# Measure.net
KiCad netlist of a schematic drawn in Altium Designer
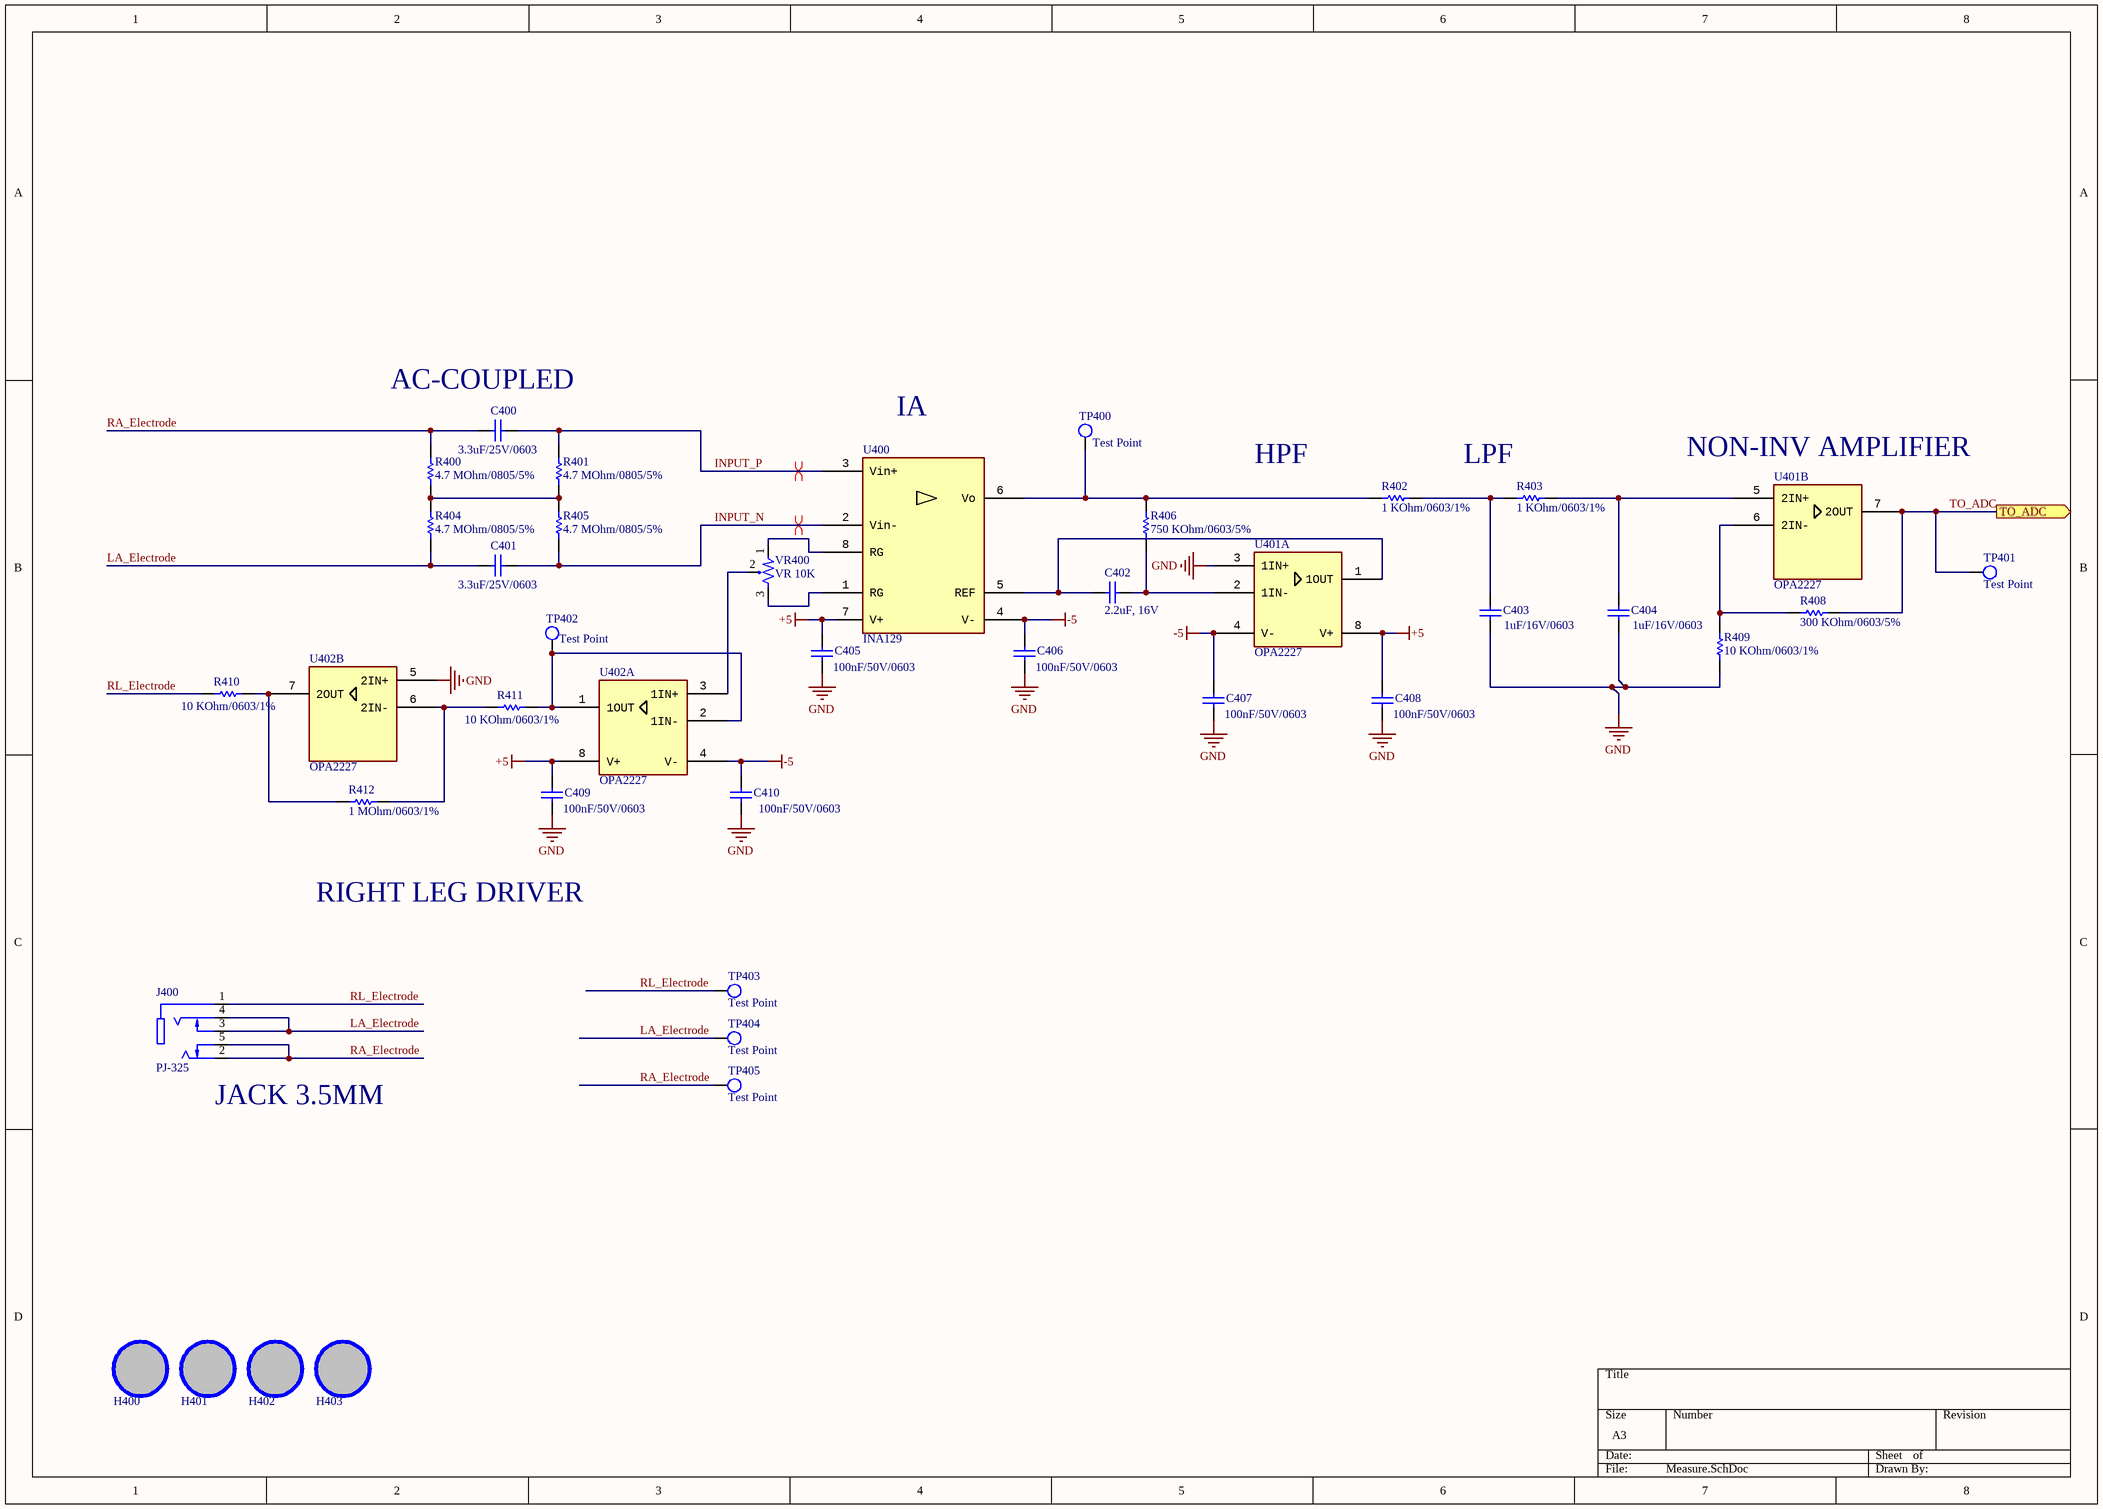
[diagram p0: Measure.SchDoc]

(export (version "E")
  (design (tool "Eeschema 10.0.6"))
  (components
    (comp (ref "C400")
      (value "3.3uF/25V/0603")
      (footprint "WCAP-CSGP_0805_H=1.25mm")
      (description "WCAP-CSGP Multilayer Ceramic Chip Capacitor, General Purpose, size 0805, X5R, 3.3uF, 25V")
      (fields
        (field (name "MANUFACTURER PART NUMBER") "885012107017")
        (field (name "MANUFACTURER") "Wurth Elektronik")
      )
      (libsource (lib "Altium_WCAP-CSGP (rev20a)") (part "885012107017"))
    )
    (comp (ref "C401")
      (value "3.3uF/25V/0603")
      (footprint "WCAP-CSGP_0805_H=1.25mm")
      (description "WCAP-CSGP Multilayer Ceramic Chip Capacitor, General Purpose, size 0805, X5R, 3.3uF, 25V")
      (fields
        (field (name "MANUFACTURER PART NUMBER") "885012107017")
        (field (name "MANUFACTURER") "Wurth Elektronik")
      )
      (libsource (lib "Altium_WCAP-CSGP (rev20a)") (part "885012107017"))
    )
    (comp (ref "C402")
      (value "2.2uF, 16V")
      (footprint "WCAP-CSGP_0603_H=0.8mm_Reflow")
      (description "WCAP-CSGP Multilayer Ceramic Chip Capacitor, General Purpose, size 0603, X5R, 2.2uF, 16V")
      (fields
        (field (name "MANUFACTURER PART NUMBER") "885012106018")
        (field (name "MANUFACTURER") "Wurth Elektronik")
      )
      (libsource (lib "Altium_WCAP-CSGP (rev20a)") (part "885012106018"))
    )
    (comp (ref "C403")
      (value "1uF/16V/0603")
      (footprint "WCAP-CSGP_0603_H=0.8mm_Reflow")
      (description "WCAP-CSGP Multilayer Ceramic Chip Capacitor, General Purpose, size 0603, X5R, 1uF, 16V")
      (fields
        (field (name "MANUFACTURER PART NUMBER") "885012106017")
        (field (name "MANUFACTURER") "Wurth Elektronik")
      )
      (libsource (lib "Altium_WCAP-CSGP (rev20a)") (part "885012106017"))
    )
    (comp (ref "C404")
      (value "1uF/16V/0603")
      (footprint "WCAP-CSGP_0603_H=0.8mm_Reflow")
      (description "WCAP-CSGP Multilayer Ceramic Chip Capacitor, General Purpose, size 0603, X5R, 1uF, 16V")
      (fields
        (field (name "MANUFACTURER PART NUMBER") "885012106017")
        (field (name "MANUFACTURER") "Wurth Elektronik")
      )
      (libsource (lib "Altium_WCAP-CSGP (rev20a)") (part "885012106017"))
    )
    (comp (ref "C405")
      (value "100nF/50V/0603")
      (footprint "WCAP-CSGP_0603_H=0.8mm_Reflow")
      (description "WCAP-CSGP Multilayer Ceramic Chip Capacitor, General Purpose, size 0603, X7R, 100nF, 25V")
      (fields
        (field (name "MANUFACTURER PART NUMBER") "885012206071")
        (field (name "MANUFACTURER") "Wurth Elektronik")
      )
      (libsource (lib "Altium_WCAP-CSGP (rev20a)") (part "885012206071"))
    )
    (comp (ref "C406")
      (value "100nF/50V/0603")
      (footprint "WCAP-CSGP_0603_H=0.8mm_Reflow")
      (description "WCAP-CSGP Multilayer Ceramic Chip Capacitor, General Purpose, size 0603, X7R, 100nF, 25V")
      (fields
        (field (name "MANUFACTURER PART NUMBER") "885012206071")
        (field (name "MANUFACTURER") "Wurth Elektronik")
      )
      (libsource (lib "Altium_WCAP-CSGP (rev20a)") (part "885012206071"))
    )
    (comp (ref "C407")
      (value "100nF/50V/0603")
      (footprint "WCAP-CSGP_0603_H=0.8mm_Reflow")
      (description "WCAP-CSGP Multilayer Ceramic Chip Capacitor, General Purpose, size 0603, X7R, 100nF, 25V")
      (fields
        (field (name "MANUFACTURER PART NUMBER") "885012206071")
        (field (name "MANUFACTURER") "Wurth Elektronik")
      )
      (libsource (lib "Altium_WCAP-CSGP (rev20a)") (part "885012206071"))
    )
    (comp (ref "C408")
      (value "100nF/50V/0603")
      (footprint "WCAP-CSGP_0603_H=0.8mm_Reflow")
      (description "WCAP-CSGP Multilayer Ceramic Chip Capacitor, General Purpose, size 0603, X7R, 100nF, 25V")
      (fields
        (field (name "MANUFACTURER PART NUMBER") "885012206071")
        (field (name "MANUFACTURER") "Wurth Elektronik")
      )
      (libsource (lib "Altium_WCAP-CSGP (rev20a)") (part "885012206071"))
    )
    (comp (ref "C409")
      (value "100nF/50V/0603")
      (footprint "WCAP-CSGP_0603_H=0.8mm_Reflow")
      (description "WCAP-CSGP Multilayer Ceramic Chip Capacitor, General Purpose, size 0603, X7R, 100nF, 25V")
      (fields
        (field (name "MANUFACTURER PART NUMBER") "885012206071")
        (field (name "MANUFACTURER") "Wurth Elektronik")
      )
      (libsource (lib "Altium_WCAP-CSGP (rev20a)") (part "885012206071"))
    )
    (comp (ref "C410")
      (value "100nF/50V/0603")
      (footprint "WCAP-CSGP_0603_H=0.8mm_Reflow")
      (description "WCAP-CSGP Multilayer Ceramic Chip Capacitor, General Purpose, size 0603, X7R, 100nF, 25V")
      (fields
        (field (name "MANUFACTURER PART NUMBER") "885012206071")
        (field (name "MANUFACTURER") "Wurth Elektronik")
      )
      (libsource (lib "Altium_WCAP-CSGP (rev20a)") (part "885012206071"))
    )
    (comp (ref "H400")
      (value "Hole")
      (footprint "LO KHOAN 3MM")
      (description "Hole 3mm")
      (libsource (lib "PIF_Library") (part "Hole"))
    )
    (comp (ref "H401")
      (value "Hole")
      (footprint "LO KHOAN 3MM")
      (description "Hole 3mm")
      (libsource (lib "PIF_Library") (part "Hole"))
    )
    (comp (ref "H402")
      (value "Hole")
      (footprint "LO KHOAN 3MM")
      (description "Hole 3mm")
      (libsource (lib "PIF_Library") (part "Hole"))
    )
    (comp (ref "H403")
      (value "Hole")
      (footprint "LO KHOAN 3MM")
      (description "Hole 3mm")
      (libsource (lib "PIF_Library") (part "Hole"))
    )
    (comp (ref "J400")
      (value "PJ-325")
      (footprint "3.5 mm, Strereo")
      (description "Jack 3.5 3-Pole 5-Pin")
      (fields (field (name "Comment") "PJ-324"))
      (libsource (lib "Giang's Libs") (part "PJ-324"))
    )
    (comp (ref "R400")
      (value "4.7 MOhm/0805/5%")
      (footprint "R0805")
      (description "Code 475, 1/8W")
      (fields (field (name "Comment") "Resistor 4.7 MOhm 0805 5%"))
      (libsource (lib "Giang_Resistor") (part "Resistor 4.7 MOhm 0805 5%"))
    )
    (comp (ref "R401")
      (value "4.7 MOhm/0805/5%")
      (footprint "R0805")
      (description "Code 475, 1/8W")
      (fields (field (name "Comment") "Resistor 4.7 MOhm 0805 5%"))
      (libsource (lib "Giang_Resistor") (part "Resistor 4.7 MOhm 0805 5%"))
    )
    (comp (ref "R402")
      (value "1 KOhm/0603/1%")
      (footprint "R0603")
      (description "Code 102, 1/10W")
      (fields (field (name "Comment") "Resistor 1 KOhm 0603 1%"))
      (libsource (lib "Giang_Resistor") (part "Resistor 1 KOhm 0603 1%"))
    )
    (comp (ref "R403")
      (value "1 KOhm/0603/1%")
      (footprint "R0603")
      (description "Code 102, 1/10W")
      (fields (field (name "Comment") "Resistor 1 KOhm 0603 1%"))
      (libsource (lib "Giang_Resistor") (part "Resistor 1 KOhm 0603 1%"))
    )
    (comp (ref "R404")
      (value "4.7 MOhm/0805/5%")
      (footprint "R0805")
      (description "Code 475, 1/8W")
      (fields (field (name "Comment") "Resistor 4.7 MOhm 0805 5%"))
      (libsource (lib "Giang_Resistor") (part "Resistor 4.7 MOhm 0805 5%"))
    )
    (comp (ref "R405")
      (value "4.7 MOhm/0805/5%")
      (footprint "R0805")
      (description "Code 475, 1/8W")
      (fields (field (name "Comment") "Resistor 4.7 MOhm 0805 5%"))
      (libsource (lib "Giang_Resistor") (part "Resistor 4.7 MOhm 0805 5%"))
    )
    (comp (ref "R406")
      (value "750 KOhm/0603/5%")
      (footprint "R0603")
      (description "Code 754, 1/10W")
      (fields (field (name "Comment") "Resistor 750 KOhm 0603 5%"))
      (libsource (lib "Giang_Resistor") (part "Resistor 750 KOhm 0603 5%"))
    )
    (comp (ref "R408")
      (value "300 KOhm/0603/5%")
      (footprint "R0603")
      (description "Code 304, 1/10W")
      (fields (field (name "Comment") "Resistor 300 KOhm 0603 5%"))
      (libsource (lib "Giang_Resistor") (part "Resistor 300 KOhm 0603 5%"))
    )
    (comp (ref "R409")
      (value "10 KOhm/0603/1%")
      (footprint "R0603")
      (description "Code 103, 1/10W")
      (fields (field (name "Comment") "Resistor 10 KOhm 0603 1%"))
      (libsource (lib "Giang_Resistor") (part "Resistor 10 KOhm 0603 1%"))
    )
    (comp (ref "R410")
      (value "10 KOhm/0603/1%")
      (footprint "R0603")
      (description "Code 103, 1/10W")
      (fields (field (name "Comment") "Resistor 10 KOhm 0603 1%"))
      (libsource (lib "Giang_Resistor") (part "Resistor 10 KOhm 0603 1%"))
    )
    (comp (ref "R411")
      (value "10 KOhm/0603/1%")
      (footprint "R0603")
      (description "Code 103, 1/10W")
      (fields (field (name "Comment") "Resistor 10 KOhm 0603 1%"))
      (libsource (lib "Giang_Resistor") (part "Resistor 10 KOhm 0603 1%"))
    )
    (comp (ref "R412")
      (value "1 MOhm/0603/1%")
      (footprint "R0603")
      (description "Code 105, 1/10W")
      (fields (field (name "Comment") "Resistor 1 MOhm 0603 1%"))
      (libsource (lib "Giang_Resistor") (part "Resistor 1 MOhm 0603 1%"))
    )
    (comp (ref "TP400")
      (value "Test Point")
      (footprint "TP")
      (libsource (lib "PIF_Library") (part "Test Point"))
    )
    (comp (ref "TP401")
      (value "Test Point")
      (footprint "TP")
      (libsource (lib "PIF_Library") (part "Test Point"))
    )
    (comp (ref "TP402")
      (value "Test Point")
      (footprint "TP")
      (libsource (lib "PIF_Library") (part "Test Point"))
    )
    (comp (ref "TP403")
      (value "Test Point")
      (footprint "TP")
      (libsource (lib "PIF_Library") (part "Test Point"))
    )
    (comp (ref "TP404")
      (value "Test Point")
      (footprint "TP")
      (libsource (lib "PIF_Library") (part "Test Point"))
    )
    (comp (ref "TP405")
      (value "Test Point")
      (footprint "TP")
      (libsource (lib "PIF_Library") (part "Test Point"))
    )
    (comp (ref "U400")
      (value "INA129")
      (footprint "SOIC-8")
      (description "Precision, Low Power Instrumentation Amplifiers")
      (libsource (lib "Giang_OPAMP") (part "INA129"))
    )
    (comp (ref "U401")
      (value "OPA2227")
      (footprint "SOIC-8")
      (description "High-Precision, Low-Noise Operational Amplifiers")
      (libsource (lib "Giang_OPAMP") (part "OPA2227"))
    )
    (comp (ref "U402")
      (value "OPA2227")
      (footprint "SOIC-8")
      (description "High-Precision, Low-Noise Operational Amplifiers")
      (libsource (lib "") (part "OPA2227_1"))
    )
    (comp (ref "VR400")
      (value "VR 10K")
      (footprint "VARISTOR 2")
      (description "Var Resistor")
      (fields (field (name "Comment") "10K"))
      (libsource (lib "PIF_Library") (part "Var Resistor"))
    )
  )
  (nets
    (net (code "1") (name "+5") (class "Default")
      (node (ref "C405") (pin "2") (pinfunction "2_2") (pintype "passive"))
      (node (ref "C408") (pin "1") (pinfunction "1_1") (pintype "passive"))
      (node (ref "C409") (pin "2") (pinfunction "2_2") (pintype "passive"))
      (node (ref "U400") (pin "7") (pinfunction "V+_7") (pintype "passive"))
      (node (ref "U401") (pin "8") (pinfunction "V+_8") (pintype "passive"))
      (node (ref "U402") (pin "8") (pinfunction "V+_8") (pintype "passive"))
    )
    (net (code "2") (name "-5") (class "Default")
      (node (ref "C406") (pin "1") (pinfunction "1_1") (pintype "passive"))
      (node (ref "C407") (pin "2") (pinfunction "2_2") (pintype "passive"))
      (node (ref "C410") (pin "1") (pinfunction "1_1") (pintype "passive"))
      (node (ref "U400") (pin "4") (pinfunction "V-_4") (pintype "passive"))
      (node (ref "U401") (pin "4") (pinfunction "V-_4") (pintype "passive"))
      (node (ref "U402") (pin "4") (pinfunction "V-_4") (pintype "passive"))
    )
    (net (code "3") (name "/INPUT_N") (class "Default")
      (node (ref "C401") (pin "2") (pinfunction "2_2") (pintype "passive"))
      (node (ref "R405") (pin "1") (pinfunction "1_1") (pintype "passive"))
      (node (ref "U400") (pin "2") (pinfunction "Vin-_2") (pintype "passive"))
    )
    (net (code "4") (name "/INPUT_P") (class "Default")
      (node (ref "C400") (pin "2") (pinfunction "2_2") (pintype "passive"))
      (node (ref "R401") (pin "2") (pinfunction "2_2") (pintype "passive"))
      (node (ref "U400") (pin "3") (pinfunction "Vin+_3") (pintype "passive"))
    )
    (net (code "5") (name "/LA_Electrode") (class "Default")
      (node (ref "C401") (pin "1") (pinfunction "1_1") (pintype "passive"))
      (node (ref "J400") (pin "3") (pinfunction "3_3") (pintype "passive"))
      (node (ref "J400") (pin "4") (pinfunction "4_4") (pintype "passive"))
      (node (ref "R404") (pin "1") (pinfunction "1_1") (pintype "passive"))
      (node (ref "TP404") (pin "TP1") (pinfunction "0_TP1") (pintype "passive"))
    )
    (net (code "6") (name "/RA_Electrode") (class "Default")
      (node (ref "C400") (pin "1") (pinfunction "1_1") (pintype "passive"))
      (node (ref "J400") (pin "2") (pinfunction "2_2") (pintype "passive"))
      (node (ref "J400") (pin "5") (pinfunction "5_5") (pintype "passive"))
      (node (ref "R400") (pin "2") (pinfunction "2_2") (pintype "passive"))
      (node (ref "TP405") (pin "TP1") (pinfunction "0_TP1") (pintype "passive"))
    )
    (net (code "7") (name "/RL_Electrode") (class "Default")
      (node (ref "J400") (pin "1") (pinfunction "1_1") (pintype "passive"))
      (node (ref "R410") (pin "1") (pinfunction "1_1") (pintype "passive"))
      (node (ref "TP403") (pin "TP1") (pinfunction "0_TP1") (pintype "passive"))
    )
    (net (code "8") (name "/TO_ADC") (class "Default")
      (node (ref "R408") (pin "2") (pinfunction "2_2") (pintype "passive"))
      (node (ref "TP401") (pin "TP1") (pinfunction "0_TP1") (pintype "passive"))
      (node (ref "U401") (pin "7") (pinfunction "2OUT_7") (pintype "passive"))
    )
    (net (code "9") (name "GND") (class "Default")
      (node (ref "C403") (pin "1") (pinfunction "1_1") (pintype "passive"))
      (node (ref "C404") (pin "1") (pinfunction "1_1") (pintype "passive"))
      (node (ref "C405") (pin "1") (pinfunction "1_1") (pintype "passive"))
      (node (ref "C406") (pin "2") (pinfunction "2_2") (pintype "passive"))
      (node (ref "C407") (pin "1") (pinfunction "1_1") (pintype "passive"))
      (node (ref "C408") (pin "2") (pinfunction "2_2") (pintype "passive"))
      (node (ref "C409") (pin "1") (pinfunction "1_1") (pintype "passive"))
      (node (ref "C410") (pin "2") (pinfunction "2_2") (pintype "passive"))
      (node (ref "R409") (pin "1") (pinfunction "1_1") (pintype "passive"))
      (node (ref "U401") (pin "3") (pinfunction "1IN+_3") (pintype "passive"))
      (node (ref "U402") (pin "5") (pinfunction "2IN+_5") (pintype "passive"))
    )
    (net (code "10") (name "Net-(C403-Pad2)") (class "Default")
      (node (ref "C403") (pin "2") (pinfunction "2_2") (pintype "passive"))
      (node (ref "R402") (pin "2") (pinfunction "2_2") (pintype "passive"))
      (node (ref "R403") (pin "1") (pinfunction "1_1") (pintype "passive"))
    )
    (net (code "11") (name "Net-(R400-Pad1)") (class "Default")
      (node (ref "R400") (pin "1") (pinfunction "1_1") (pintype "passive"))
      (node (ref "R401") (pin "1") (pinfunction "1_1") (pintype "passive"))
      (node (ref "R404") (pin "2") (pinfunction "2_2") (pintype "passive"))
      (node (ref "R405") (pin "2") (pinfunction "2_2") (pintype "passive"))
    )
    (net (code "12") (name "Net-(TP400-0)") (class "Default")
      (node (ref "R402") (pin "1") (pinfunction "1_1") (pintype "passive"))
      (node (ref "R406") (pin "2") (pinfunction "2_2") (pintype "passive"))
      (node (ref "TP400") (pin "TP1") (pinfunction "0_TP1") (pintype "passive"))
      (node (ref "U400") (pin "6") (pinfunction "Vo_6") (pintype "passive"))
    )
    (net (code "13") (name "Net-(TP402-0)") (class "Default")
      (node (ref "R411") (pin "2") (pinfunction "2_2") (pintype "passive"))
      (node (ref "TP402") (pin "TP1") (pinfunction "0_TP1") (pintype "passive"))
      (node (ref "U402") (pin "1") (pinfunction "1OUT_1") (pintype "passive"))
      (node (ref "U402") (pin "2") (pinfunction "1IN-_2") (pintype "passive"))
    )
    (net (code "14") (name "Net-(U400-REF)") (class "Default")
      (node (ref "C402") (pin "2") (pinfunction "2_2") (pintype "passive"))
      (node (ref "U400") (pin "5") (pinfunction "REF_5") (pintype "passive"))
      (node (ref "U401") (pin "1") (pinfunction "1OUT_1") (pintype "passive"))
    )
    (net (code "15") (name "Net-(U400-RG-Pad1)") (class "Default")
      (node (ref "U400") (pin "1") (pinfunction "RG_1") (pintype "passive"))
      (node (ref "VR400") (pin "3") (pinfunction "3_3") (pintype "passive"))
    )
    (net (code "16") (name "Net-(U400-RG-Pad8)") (class "Default")
      (node (ref "U400") (pin "8") (pinfunction "RG_8") (pintype "passive"))
      (node (ref "VR400") (pin "1") (pinfunction "1_1") (pintype "passive"))
    )
    (net (code "17") (name "Net-(U401A-1IN-)") (class "Default")
      (node (ref "C402") (pin "1") (pinfunction "1_1") (pintype "passive"))
      (node (ref "R406") (pin "1") (pinfunction "1_1") (pintype "passive"))
      (node (ref "U401") (pin "2") (pinfunction "1IN-_2") (pintype "passive"))
    )
    (net (code "18") (name "Net-(U401B-2IN+)") (class "Default")
      (node (ref "C404") (pin "2") (pinfunction "2_2") (pintype "passive"))
      (node (ref "R403") (pin "2") (pinfunction "2_2") (pintype "passive"))
      (node (ref "U401") (pin "5") (pinfunction "2IN+_5") (pintype "passive"))
    )
    (net (code "19") (name "Net-(U401B-2IN-)") (class "Default")
      (node (ref "R408") (pin "1") (pinfunction "1_1") (pintype "passive"))
      (node (ref "R409") (pin "2") (pinfunction "2_2") (pintype "passive"))
      (node (ref "U401") (pin "6") (pinfunction "2IN-_6") (pintype "passive"))
    )
    (net (code "20") (name "Net-(U402A-1IN+)") (class "Default")
      (node (ref "U402") (pin "3") (pinfunction "1IN+_3") (pintype "passive"))
      (node (ref "VR400") (pin "2") (pinfunction "2_2") (pintype "passive"))
    )
    (net (code "21") (name "Net-(U402B-2IN-)") (class "Default")
      (node (ref "R411") (pin "1") (pinfunction "1_1") (pintype "passive"))
      (node (ref "R412") (pin "2") (pinfunction "2_2") (pintype "passive"))
      (node (ref "U402") (pin "6") (pinfunction "2IN-_6") (pintype "passive"))
    )
    (net (code "22") (name "Net-(U402B-2OUT)") (class "Default")
      (node (ref "R410") (pin "2") (pinfunction "2_2") (pintype "passive"))
      (node (ref "R412") (pin "1") (pinfunction "1_1") (pintype "passive"))
      (node (ref "U402") (pin "7") (pinfunction "2OUT_7") (pintype "passive"))
    )
    (net (code "23") (name "unconnected-(H400-Pad1)") (class "Default")
      (node (ref "H400") (pin "1") (pinfunction "1_1") (pintype "passive"))
    )
    (net (code "24") (name "unconnected-(H401-Pad1)") (class "Default")
      (node (ref "H401") (pin "1") (pinfunction "1_1") (pintype "passive"))
    )
    (net (code "25") (name "unconnected-(H402-Pad1)") (class "Default")
      (node (ref "H402") (pin "1") (pinfunction "1_1") (pintype "passive"))
    )
    (net (code "26") (name "unconnected-(H403-Pad1)") (class "Default")
      (node (ref "H403") (pin "1") (pinfunction "1_1") (pintype "passive"))
    )
  )
)
